# Filters.net
KiCad netlist of a schematic drawn in Altium Designer
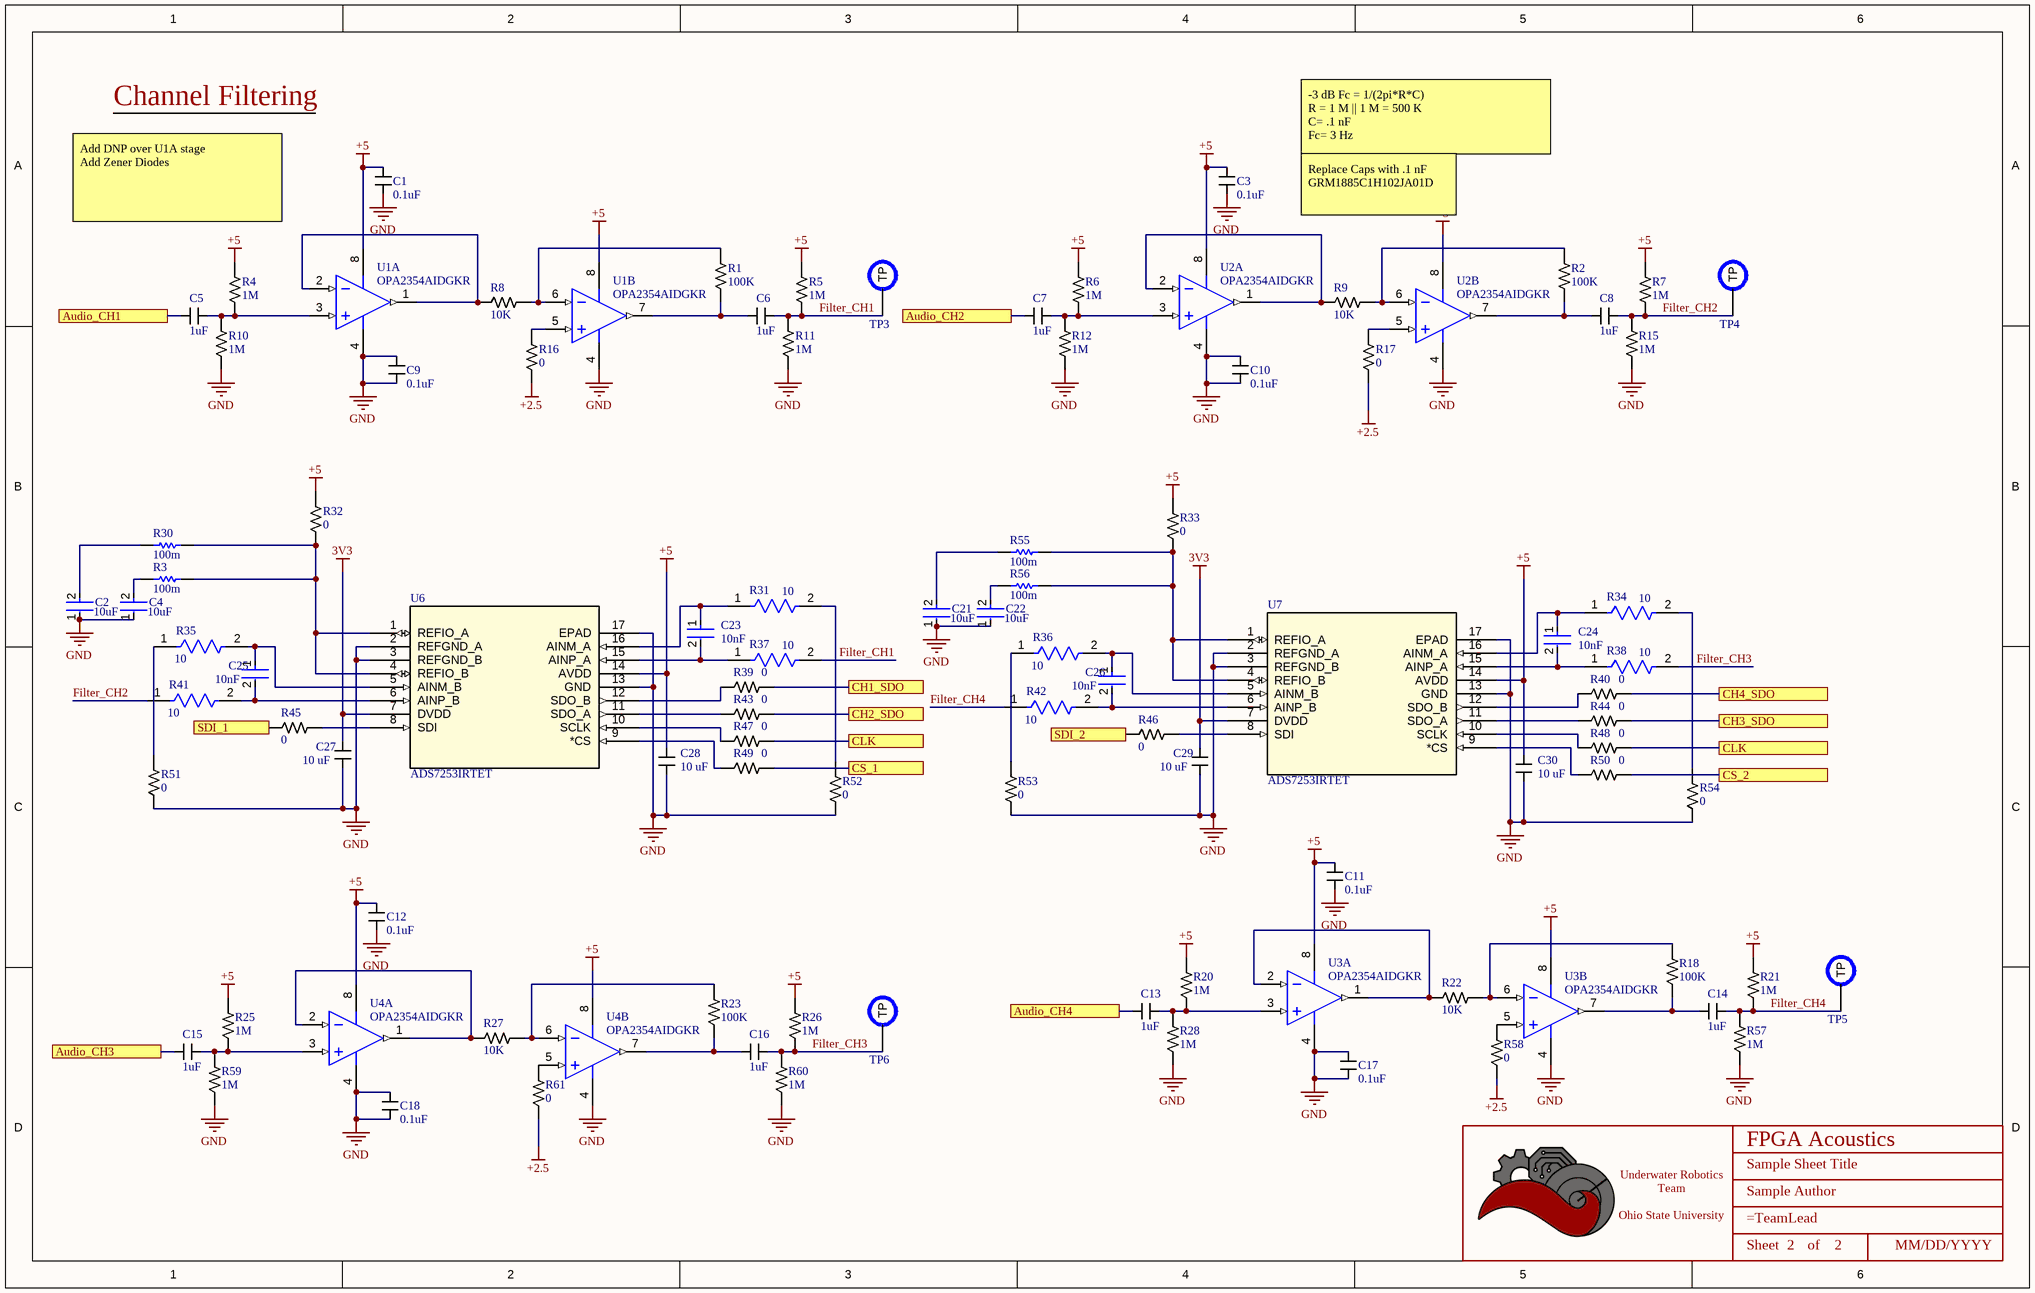
[diagram p0: Filters.SchDoc]

(export (version "E")
  (design (tool "Eeschema 10.0.6"))
  (components
    (comp (ref "C1")
      (value "0.1uF")
      (footprint "CAPACITOR_0603")
      (description "Cap 100nF 25V +/-10%\r\nCeramic 0603")
      (fields
        (field (name "TOLERANCE") "+/- 10%")
        (field (name "VOLTAGE") "6.3V")
        (field (name "MADE BY") "Flip B")
      )
      (libsource (lib "Capacitors") (part "CAPACITOR_0.1uF_0603_25V"))
    )
    (comp (ref "C2")
      (value "10uF")
      (footprint "FP-CL21B106KOQNNNE-MFG")
      (description "CAP CER 10UF 16V X7R 0805")
      (fields
        (field (name "MANUFACTURER PART NUMBER") "CL21B106KOQNNNE")
        (field (name "OCTOPART") "https://octopart.com/cl21b106koqnnne-samsung-19832289")
      )
      (libsource (lib "Altium Content Vault") (part "236180d848d6139a670b325ea6854c9"))
    )
    (comp (ref "C3")
      (value "0.1uF")
      (footprint "CAPACITOR_0603")
      (description "Cap 100nF 25V +/-10%\r\nCeramic 0603")
      (fields
        (field (name "TOLERANCE") "+/- 10%")
        (field (name "VOLTAGE") "6.3V")
        (field (name "MADE BY") "Flip B")
      )
      (libsource (lib "Capacitors") (part "CAPACITOR_0.1uF_0603_25V"))
    )
    (comp (ref "C4")
      (value "10uF")
      (footprint "FP-CL21B106KOQNNNE-MFG")
      (description "CAP CER 10UF 16V X7R 0805")
      (fields
        (field (name "MANUFACTURER PART NUMBER") "CL21B106KOQNNNE")
        (field (name "OCTOPART") "https://octopart.com/cl21b106koqnnne-samsung-19832289")
      )
      (libsource (lib "Altium Content Vault") (part "236180d848d6139a670b325ea6854c9"))
    )
    (comp (ref "C5")
      (value "1uF")
      (footprint "CAPACITOR_0603")
      (description "Cap 1uF 16V +/-10%\r\nCeramic 0603")
      (fields
        (field (name "TOLERANCE") "+/- 10%")
        (field (name "VOLTAGE") "16V")
        (field (name "MADE BY") "Flip B")
      )
      (libsource (lib "Capacitors") (part "CAPACITOR_1uF_0603"))
    )
    (comp (ref "C6")
      (value "1uF")
      (footprint "CAPACITOR_0603")
      (description "Cap 1uF 16V +/-10%\r\nCeramic 0603")
      (fields
        (field (name "TOLERANCE") "+/- 10%")
        (field (name "VOLTAGE") "16V")
        (field (name "MADE BY") "Flip B")
      )
      (libsource (lib "Capacitors") (part "CAPACITOR_1uF_0603"))
    )
    (comp (ref "C7")
      (value "1uF")
      (footprint "CAPACITOR_0603")
      (description "Cap 1uF 16V +/-10%\r\nCeramic 0603")
      (fields
        (field (name "TOLERANCE") "+/- 10%")
        (field (name "VOLTAGE") "16V")
        (field (name "MADE BY") "Flip B")
      )
      (libsource (lib "Capacitors") (part "CAPACITOR_1uF_0603"))
    )
    (comp (ref "C8")
      (value "1uF")
      (footprint "CAPACITOR_0603")
      (description "Cap 1uF 16V +/-10%\r\nCeramic 0603")
      (fields
        (field (name "TOLERANCE") "+/- 10%")
        (field (name "VOLTAGE") "16V")
        (field (name "MADE BY") "Flip B")
      )
      (libsource (lib "Capacitors") (part "CAPACITOR_1uF_0603"))
    )
    (comp (ref "C9")
      (value "0.1uF")
      (footprint "CAPACITOR_0603")
      (description "Cap 100nF 25V +/-10%\r\nCeramic 0603")
      (fields
        (field (name "TOLERANCE") "+/- 10%")
        (field (name "VOLTAGE") "6.3V")
        (field (name "MADE BY") "Flip B")
      )
      (libsource (lib "Capacitors") (part "CAPACITOR_0.1uF_0603_25V"))
    )
    (comp (ref "C10")
      (value "0.1uF")
      (footprint "CAPACITOR_0603")
      (description "Cap 100nF 25V +/-10%\r\nCeramic 0603")
      (fields
        (field (name "TOLERANCE") "+/- 10%")
        (field (name "VOLTAGE") "6.3V")
        (field (name "MADE BY") "Flip B")
      )
      (libsource (lib "Capacitors") (part "CAPACITOR_0.1uF_0603_25V"))
    )
    (comp (ref "C11")
      (value "0.1uF")
      (footprint "CAPACITOR_0603")
      (description "Cap 100nF 25V +/-10%\r\nCeramic 0603")
      (fields
        (field (name "TOLERANCE") "+/- 10%")
        (field (name "VOLTAGE") "6.3V")
        (field (name "MADE BY") "Flip B")
      )
      (libsource (lib "Capacitors") (part "CAPACITOR_0.1uF_0603_25V"))
    )
    (comp (ref "C12")
      (value "0.1uF")
      (footprint "CAPACITOR_0603")
      (description "Cap 100nF 25V +/-10%\r\nCeramic 0603")
      (fields
        (field (name "TOLERANCE") "+/- 10%")
        (field (name "VOLTAGE") "6.3V")
        (field (name "MADE BY") "Flip B")
      )
      (libsource (lib "Capacitors") (part "CAPACITOR_0.1uF_0603_25V"))
    )
    (comp (ref "C13")
      (value "1uF")
      (footprint "CAPACITOR_0603")
      (description "Cap 1uF 16V +/-10%\r\nCeramic 0603")
      (fields
        (field (name "TOLERANCE") "+/- 10%")
        (field (name "VOLTAGE") "16V")
        (field (name "MADE BY") "Flip B")
      )
      (libsource (lib "Capacitors") (part "CAPACITOR_1uF_0603"))
    )
    (comp (ref "C14")
      (value "1uF")
      (footprint "CAPACITOR_0603")
      (description "Cap 1uF 16V +/-10%\r\nCeramic 0603")
      (fields
        (field (name "TOLERANCE") "+/- 10%")
        (field (name "VOLTAGE") "16V")
        (field (name "MADE BY") "Flip B")
      )
      (libsource (lib "Capacitors") (part "CAPACITOR_1uF_0603"))
    )
    (comp (ref "C15")
      (value "1uF")
      (footprint "CAPACITOR_0603")
      (description "Cap 1uF 16V +/-10%\r\nCeramic 0603")
      (fields
        (field (name "TOLERANCE") "+/- 10%")
        (field (name "VOLTAGE") "16V")
        (field (name "MADE BY") "Flip B")
      )
      (libsource (lib "Capacitors") (part "CAPACITOR_1uF_0603"))
    )
    (comp (ref "C16")
      (value "1uF")
      (footprint "CAPACITOR_0603")
      (description "Cap 1uF 16V +/-10%\r\nCeramic 0603")
      (fields
        (field (name "TOLERANCE") "+/- 10%")
        (field (name "VOLTAGE") "16V")
        (field (name "MADE BY") "Flip B")
      )
      (libsource (lib "Capacitors") (part "CAPACITOR_1uF_0603"))
    )
    (comp (ref "C17")
      (value "0.1uF")
      (footprint "CAPACITOR_0603")
      (description "Cap 100nF 25V +/-10%\r\nCeramic 0603")
      (fields
        (field (name "TOLERANCE") "+/- 10%")
        (field (name "VOLTAGE") "6.3V")
        (field (name "MADE BY") "Flip B")
      )
      (libsource (lib "Capacitors") (part "CAPACITOR_0.1uF_0603_25V"))
    )
    (comp (ref "C18")
      (value "0.1uF")
      (footprint "CAPACITOR_0603")
      (description "Cap 100nF 25V +/-10%\r\nCeramic 0603")
      (fields
        (field (name "TOLERANCE") "+/- 10%")
        (field (name "VOLTAGE") "6.3V")
        (field (name "MADE BY") "Flip B")
      )
      (libsource (lib "Capacitors") (part "CAPACITOR_0.1uF_0603_25V"))
    )
    (comp (ref "C21")
      (value "10uF")
      (footprint "FP-CL21B106KOQNNNE-MFG")
      (description "CAP CER 10UF 16V X7R 0805")
      (fields
        (field (name "MANUFACTURER PART NUMBER") "CL21B106KOQNNNE")
        (field (name "OCTOPART") "https://octopart.com/cl21b106koqnnne-samsung-19832289")
      )
      (libsource (lib "Altium Content Vault") (part "236180d848d6139a670b325ea6854c9"))
    )
    (comp (ref "C22")
      (value "10uF")
      (footprint "FP-CL21B106KOQNNNE-MFG")
      (description "CAP CER 10UF 16V X7R 0805")
      (fields
        (field (name "MANUFACTURER PART NUMBER") "CL21B106KOQNNNE")
        (field (name "OCTOPART") "https://octopart.com/cl21b106koqnnne-samsung-19832289")
      )
      (libsource (lib "Altium Content Vault") (part "236180d848d6139a670b325ea6854c9"))
    )
    (comp (ref "C23")
      (value "GRM2195C1H103JA01D")
      (footprint "FP-GRM219-0_1-IPC_B")
      (description "Chip Multilayer Ceramic Capacitors for General Purpose, 0805, 10000pF, C0G, 30ppm/°C, 5%, 50V")
      (fields
        (field (name "VOLTAGE") "50V")
        (field (name "TOLERANCE") "5%")
        (field (name "CAPACITANCE") "10nF")
      )
      (libsource (lib "Altium Content Vault") (part "02cd4be3c70576c341d710602a673aa"))
    )
    (comp (ref "C24")
      (value "GRM2195C1H103JA01D")
      (footprint "FP-GRM219-0_1-IPC_B")
      (description "Chip Multilayer Ceramic Capacitors for General Purpose, 0805, 10000pF, C0G, 30ppm/°C, 5%, 50V")
      (fields
        (field (name "VOLTAGE") "50V")
        (field (name "TOLERANCE") "5%")
        (field (name "CAPACITANCE") "10nF")
      )
      (libsource (lib "Altium Content Vault") (part "02cd4be3c70576c341d710602a673aa"))
    )
    (comp (ref "C25")
      (value "GRM2195C1H103JA01D")
      (footprint "FP-GRM219-0_1-IPC_B")
      (description "Chip Multilayer Ceramic Capacitors for General Purpose, 0805, 10000pF, C0G, 30ppm/°C, 5%, 50V")
      (fields
        (field (name "VOLTAGE") "50V")
        (field (name "TOLERANCE") "5%")
        (field (name "CAPACITANCE") "10nF")
      )
      (libsource (lib "Altium Content Vault") (part "02cd4be3c70576c341d710602a673aa"))
    )
    (comp (ref "C26")
      (value "GRM2195C1H103JA01D")
      (footprint "FP-GRM219-0_1-IPC_B")
      (description "Chip Multilayer Ceramic Capacitors for General Purpose, 0805, 10000pF, C0G, 30ppm/°C, 5%, 50V")
      (fields
        (field (name "VOLTAGE") "50V")
        (field (name "TOLERANCE") "5%")
        (field (name "CAPACITANCE") "10nF")
      )
      (libsource (lib "Altium Content Vault") (part "02cd4be3c70576c341d710602a673aa"))
    )
    (comp (ref "C27")
      (value "10uF Ceramic 6.3V")
      (footprint "CAPACITOR_0603")
      (description "Cap 10uF 6.3V +/-20%\r\nCeramic 0603")
      (fields
        (field (name "TOLERANCE") "+/- 20%")
        (field (name "VOLTAGE") "6.3V")
        (field (name "VALUE (UF)") "10 uF")
        (field (name "MADE BY") "Flip B")
      )
      (libsource (lib "Capacitors") (part "CAPACITOR_10uF_0603"))
    )
    (comp (ref "C28")
      (value "10uF Ceramic 6.3V")
      (footprint "CAPACITOR_0603")
      (description "Cap 10uF 6.3V +/-20%\r\nCeramic 0603")
      (fields
        (field (name "TOLERANCE") "+/- 20%")
        (field (name "VOLTAGE") "6.3V")
        (field (name "VALUE (UF)") "10 uF")
        (field (name "MADE BY") "Flip B")
      )
      (libsource (lib "Capacitors") (part "CAPACITOR_10uF_0603"))
    )
    (comp (ref "C29")
      (value "10uF Ceramic 6.3V")
      (footprint "CAPACITOR_0603")
      (description "Cap 10uF 6.3V +/-20%\r\nCeramic 0603")
      (fields
        (field (name "TOLERANCE") "+/- 20%")
        (field (name "VOLTAGE") "6.3V")
        (field (name "VALUE (UF)") "10 uF")
        (field (name "MADE BY") "Flip B")
      )
      (libsource (lib "Capacitors") (part "CAPACITOR_10uF_0603"))
    )
    (comp (ref "C30")
      (value "10uF Ceramic 6.3V")
      (footprint "CAPACITOR_0603")
      (description "Cap 10uF 6.3V +/-20%\r\nCeramic 0603")
      (fields
        (field (name "TOLERANCE") "+/- 20%")
        (field (name "VOLTAGE") "6.3V")
        (field (name "VALUE (UF)") "10 uF")
        (field (name "MADE BY") "Flip B")
      )
      (libsource (lib "Capacitors") (part "CAPACITOR_10uF_0603"))
    )
    (comp (ref "R1")
      (value "100k Ohm 1% 1/16W")
      (footprint "RESISTOR_0402")
      (description "RES 100k OHM 1% 1/16W 0402")
      (fields
        (field (name "TOLERANCE") "+/- 1%")
        (field (name "VALUE  (OHMS)") "100K")
        (field (name "MADE BY") "Robert Pafford")
      )
      (libsource (lib "Resistors") (part "RESISTOR_100K_0402"))
    )
    (comp (ref "R2")
      (value "100k Ohm 1% 1/16W")
      (footprint "RESISTOR_0402")
      (description "RES 100k OHM 1% 1/16W 0402")
      (fields
        (field (name "TOLERANCE") "+/- 1%")
        (field (name "VALUE  (OHMS)") "100K")
        (field (name "MADE BY") "Robert Pafford")
      )
      (libsource (lib "Resistors") (part "RESISTOR_100K_0402"))
    )
    (comp (ref "R3")
      (value "100m")
      (footprint "RESC1005X40X25NL10T10")
      (fields (field (name "MANUFACTURER") "Yageo") (field (name "PART NUMBER") "RL0402JR-070R1L"))
      (libsource (lib "Altium Content Vault") (part "RES"))
    )
    (comp (ref "R4")
      (value "1M Ohm 1% 1/16W")
      (footprint "RESISTOR_0402")
      (description "RES 1M OHM 1% 1/16W 0402")
      (fields
        (field (name "TOLERANCE") "+/- 1%")
        (field (name "VALUE  (OHMS)") "1M")
        (field (name "MADE BY") "Robert Pafford")
      )
      (libsource (lib "Resistors") (part "RESISTOR_1M_0402"))
    )
    (comp (ref "R5")
      (value "1M Ohm 1% 1/16W")
      (footprint "RESISTOR_0402")
      (description "RES 1M OHM 1% 1/16W 0402")
      (fields
        (field (name "TOLERANCE") "+/- 1%")
        (field (name "VALUE  (OHMS)") "1M")
        (field (name "MADE BY") "Robert Pafford")
      )
      (libsource (lib "Resistors") (part "RESISTOR_1M_0402"))
    )
    (comp (ref "R6")
      (value "1M Ohm 1% 1/16W")
      (footprint "RESISTOR_0402")
      (description "RES 1M OHM 1% 1/16W 0402")
      (fields
        (field (name "TOLERANCE") "+/- 1%")
        (field (name "VALUE  (OHMS)") "1M")
        (field (name "MADE BY") "Robert Pafford")
      )
      (libsource (lib "Resistors") (part "RESISTOR_1M_0402"))
    )
    (comp (ref "R7")
      (value "1M Ohm 1% 1/16W")
      (footprint "RESISTOR_0402")
      (description "RES 1M OHM 1% 1/16W 0402")
      (fields
        (field (name "TOLERANCE") "+/- 1%")
        (field (name "VALUE  (OHMS)") "1M")
        (field (name "MADE BY") "Robert Pafford")
      )
      (libsource (lib "Resistors") (part "RESISTOR_1M_0402"))
    )
    (comp (ref "R8")
      (value "10k Ohm 1% 1/16W")
      (footprint "RESISTOR_0402")
      (description "RES 10k OHM 1% 1/16W 0402")
      (fields
        (field (name "TOLERANCE") "+/- 1%")
        (field (name "VALUE  (OHMS)") "10K")
        (field (name "MADE BY") "Robert Pafford")
      )
      (libsource (lib "Resistors") (part "RESISTOR_10K_0402"))
    )
    (comp (ref "R9")
      (value "10k Ohm 1% 1/16W")
      (footprint "RESISTOR_0402")
      (description "RES 10k OHM 1% 1/16W 0402")
      (fields
        (field (name "TOLERANCE") "+/- 1%")
        (field (name "VALUE  (OHMS)") "10K")
        (field (name "MADE BY") "Robert Pafford")
      )
      (libsource (lib "Resistors") (part "RESISTOR_10K_0402"))
    )
    (comp (ref "R10")
      (value "1M Ohm 1% 1/16W")
      (footprint "RESISTOR_0402")
      (description "RES 1M OHM 1% 1/16W 0402")
      (fields
        (field (name "TOLERANCE") "+/- 1%")
        (field (name "VALUE  (OHMS)") "1M")
        (field (name "MADE BY") "Robert Pafford")
      )
      (libsource (lib "Resistors") (part "RESISTOR_1M_0402"))
    )
    (comp (ref "R11")
      (value "1M Ohm 1% 1/16W")
      (footprint "RESISTOR_0402")
      (description "RES 1M OHM 1% 1/16W 0402")
      (fields
        (field (name "TOLERANCE") "+/- 1%")
        (field (name "VALUE  (OHMS)") "1M")
        (field (name "MADE BY") "Robert Pafford")
      )
      (libsource (lib "Resistors") (part "RESISTOR_1M_0402"))
    )
    (comp (ref "R12")
      (value "1M Ohm 1% 1/16W")
      (footprint "RESISTOR_0402")
      (description "RES 1M OHM 1% 1/16W 0402")
      (fields
        (field (name "TOLERANCE") "+/- 1%")
        (field (name "VALUE  (OHMS)") "1M")
        (field (name "MADE BY") "Robert Pafford")
      )
      (libsource (lib "Resistors") (part "RESISTOR_1M_0402"))
    )
    (comp (ref "R15")
      (value "1M Ohm 1% 1/16W")
      (footprint "RESISTOR_0402")
      (description "RES 1M OHM 1% 1/16W 0402")
      (fields
        (field (name "TOLERANCE") "+/- 1%")
        (field (name "VALUE  (OHMS)") "1M")
        (field (name "MADE BY") "Robert Pafford")
      )
      (libsource (lib "Resistors") (part "RESISTOR_1M_0402"))
    )
    (comp (ref "R16")
      (value "0 Ohm 1% 1/16W")
      (footprint "RESISTOR_0402")
      (description "RES 0 OHM 1% 1/16W 0402")
      (fields
        (field (name "TOLERANCE") "+/- 1%")
        (field (name "VALUE  (OHMS)") "0")
        (field (name "MADE BY") "Robert Pafford")
      )
      (libsource (lib "Resistors") (part "RESISTOR_0_0402"))
    )
    (comp (ref "R17")
      (value "0 Ohm 1% 1/16W")
      (footprint "RESISTOR_0402")
      (description "RES 0 OHM 1% 1/16W 0402")
      (fields
        (field (name "TOLERANCE") "+/- 1%")
        (field (name "VALUE  (OHMS)") "0")
        (field (name "MADE BY") "Robert Pafford")
      )
      (libsource (lib "Resistors") (part "RESISTOR_0_0402"))
    )
    (comp (ref "R18")
      (value "100k Ohm 1% 1/16W")
      (footprint "RESISTOR_0402")
      (description "RES 100k OHM 1% 1/16W 0402")
      (fields
        (field (name "TOLERANCE") "+/- 1%")
        (field (name "VALUE  (OHMS)") "100K")
        (field (name "MADE BY") "Robert Pafford")
      )
      (libsource (lib "Resistors") (part "RESISTOR_100K_0402"))
    )
    (comp (ref "R20")
      (value "1M Ohm 1% 1/16W")
      (footprint "RESISTOR_0402")
      (description "RES 1M OHM 1% 1/16W 0402")
      (fields
        (field (name "TOLERANCE") "+/- 1%")
        (field (name "VALUE  (OHMS)") "1M")
        (field (name "MADE BY") "Robert Pafford")
      )
      (libsource (lib "Resistors") (part "RESISTOR_1M_0402"))
    )
    (comp (ref "R21")
      (value "1M Ohm 1% 1/16W")
      (footprint "RESISTOR_0402")
      (description "RES 1M OHM 1% 1/16W 0402")
      (fields
        (field (name "TOLERANCE") "+/- 1%")
        (field (name "VALUE  (OHMS)") "1M")
        (field (name "MADE BY") "Robert Pafford")
      )
      (libsource (lib "Resistors") (part "RESISTOR_1M_0402"))
    )
    (comp (ref "R22")
      (value "10k Ohm 1% 1/16W")
      (footprint "RESISTOR_0402")
      (description "RES 10k OHM 1% 1/16W 0402")
      (fields
        (field (name "TOLERANCE") "+/- 1%")
        (field (name "VALUE  (OHMS)") "10K")
        (field (name "MADE BY") "Robert Pafford")
      )
      (libsource (lib "Resistors") (part "RESISTOR_10K_0402"))
    )
    (comp (ref "R23")
      (value "100k Ohm 1% 1/16W")
      (footprint "RESISTOR_0402")
      (description "RES 100k OHM 1% 1/16W 0402")
      (fields
        (field (name "TOLERANCE") "+/- 1%")
        (field (name "VALUE  (OHMS)") "100K")
        (field (name "MADE BY") "Robert Pafford")
      )
      (libsource (lib "Resistors") (part "RESISTOR_100K_0402"))
    )
    (comp (ref "R25")
      (value "1M Ohm 1% 1/16W")
      (footprint "RESISTOR_0402")
      (description "RES 1M OHM 1% 1/16W 0402")
      (fields
        (field (name "TOLERANCE") "+/- 1%")
        (field (name "VALUE  (OHMS)") "1M")
        (field (name "MADE BY") "Robert Pafford")
      )
      (libsource (lib "Resistors") (part "RESISTOR_1M_0402"))
    )
    (comp (ref "R26")
      (value "1M Ohm 1% 1/16W")
      (footprint "RESISTOR_0402")
      (description "RES 1M OHM 1% 1/16W 0402")
      (fields
        (field (name "TOLERANCE") "+/- 1%")
        (field (name "VALUE  (OHMS)") "1M")
        (field (name "MADE BY") "Robert Pafford")
      )
      (libsource (lib "Resistors") (part "RESISTOR_1M_0402"))
    )
    (comp (ref "R27")
      (value "10k Ohm 1% 1/16W")
      (footprint "RESISTOR_0402")
      (description "RES 10k OHM 1% 1/16W 0402")
      (fields
        (field (name "TOLERANCE") "+/- 1%")
        (field (name "VALUE  (OHMS)") "10K")
        (field (name "MADE BY") "Robert Pafford")
      )
      (libsource (lib "Resistors") (part "RESISTOR_10K_0402"))
    )
    (comp (ref "R28")
      (value "1M Ohm 1% 1/16W")
      (footprint "RESISTOR_0402")
      (description "RES 1M OHM 1% 1/16W 0402")
      (fields
        (field (name "TOLERANCE") "+/- 1%")
        (field (name "VALUE  (OHMS)") "1M")
        (field (name "MADE BY") "Robert Pafford")
      )
      (libsource (lib "Resistors") (part "RESISTOR_1M_0402"))
    )
    (comp (ref "R30")
      (value "100m")
      (footprint "RESC1005X40X25NL10T10")
      (fields (field (name "MANUFACTURER") "Yageo") (field (name "PART NUMBER") "RL0402JR-070R1L"))
      (libsource (lib "Altium Content Vault") (part "RES"))
    )
    (comp (ref "R31")
      (value "RMCF0603FT10R0")
      (footprint "FP-RMCF0603-MFG")
      (description "10Ω ±1% 0.1W 0603 Thick Film Chip Resistor AEC-Q200 compliant")
      (fields (field (name "TOLERANCE") "1%") (field (name "RESISTANCE") "10"))
      (libsource (lib "Altium Content Vault") (part "1029c3af85768c4190bb7ad29bc67b5"))
    )
    (comp (ref "R32")
      (value "0 Ohm 1% 1/16W")
      (footprint "RESISTOR_0402")
      (description "RES 0 OHM 1% 1/16W 0402")
      (fields
        (field (name "TOLERANCE") "+/- 1%")
        (field (name "VALUE  (OHMS)") "0")
        (field (name "MADE BY") "Robert Pafford")
      )
      (libsource (lib "Resistors") (part "RESISTOR_0_0402"))
    )
    (comp (ref "R33")
      (value "0 Ohm 1% 1/16W")
      (footprint "RESISTOR_0402")
      (description "RES 0 OHM 1% 1/16W 0402")
      (fields
        (field (name "TOLERANCE") "+/- 1%")
        (field (name "VALUE  (OHMS)") "0")
        (field (name "MADE BY") "Robert Pafford")
      )
      (libsource (lib "Resistors") (part "RESISTOR_0_0402"))
    )
    (comp (ref "R34")
      (value "RMCF0603FT10R0")
      (footprint "FP-RMCF0603-MFG")
      (description "10Ω ±1% 0.1W 0603 Thick Film Chip Resistor AEC-Q200 compliant")
      (fields (field (name "TOLERANCE") "1%") (field (name "RESISTANCE") "10"))
      (libsource (lib "Altium Content Vault") (part "1029c3af85768c4190bb7ad29bc67b5"))
    )
    (comp (ref "R35")
      (value "RMCF0603FT10R0")
      (footprint "FP-RMCF0603-MFG")
      (description "10Ω ±1% 0.1W 0603 Thick Film Chip Resistor AEC-Q200 compliant")
      (fields (field (name "TOLERANCE") "1%") (field (name "RESISTANCE") "10"))
      (libsource (lib "Altium Content Vault") (part "1029c3af85768c4190bb7ad29bc67b5"))
    )
    (comp (ref "R36")
      (value "RMCF0603FT10R0")
      (footprint "FP-RMCF0603-MFG")
      (description "10Ω ±1% 0.1W 0603 Thick Film Chip Resistor AEC-Q200 compliant")
      (fields (field (name "TOLERANCE") "1%") (field (name "RESISTANCE") "10"))
      (libsource (lib "Altium Content Vault") (part "1029c3af85768c4190bb7ad29bc67b5"))
    )
    (comp (ref "R37")
      (value "RMCF0603FT10R0")
      (footprint "FP-RMCF0603-MFG")
      (description "10Ω ±1% 0.1W 0603 Thick Film Chip Resistor AEC-Q200 compliant")
      (fields (field (name "TOLERANCE") "1%") (field (name "RESISTANCE") "10"))
      (libsource (lib "Altium Content Vault") (part "1029c3af85768c4190bb7ad29bc67b5"))
    )
    (comp (ref "R38")
      (value "RMCF0603FT10R0")
      (footprint "FP-RMCF0603-MFG")
      (description "10Ω ±1% 0.1W 0603 Thick Film Chip Resistor AEC-Q200 compliant")
      (fields (field (name "TOLERANCE") "1%") (field (name "RESISTANCE") "10"))
      (libsource (lib "Altium Content Vault") (part "1029c3af85768c4190bb7ad29bc67b5"))
    )
    (comp (ref "R39")
      (value "0 Ohm 1% 1/16W")
      (footprint "RESISTOR_0402")
      (description "RES 0 OHM 1% 1/16W 0402")
      (fields
        (field (name "TOLERANCE") "+/- 1%")
        (field (name "VALUE  (OHMS)") "0")
        (field (name "MADE BY") "Robert Pafford")
      )
      (libsource (lib "Resistors") (part "RESISTOR_0_0402"))
    )
    (comp (ref "R40")
      (value "0 Ohm 1% 1/16W")
      (footprint "RESISTOR_0402")
      (description "RES 0 OHM 1% 1/16W 0402")
      (fields
        (field (name "TOLERANCE") "+/- 1%")
        (field (name "VALUE  (OHMS)") "0")
        (field (name "MADE BY") "Robert Pafford")
      )
      (libsource (lib "Resistors") (part "RESISTOR_0_0402"))
    )
    (comp (ref "R41")
      (value "RMCF0603FT10R0")
      (footprint "FP-RMCF0603-MFG")
      (description "10Ω ±1% 0.1W 0603 Thick Film Chip Resistor AEC-Q200 compliant")
      (fields (field (name "TOLERANCE") "1%") (field (name "RESISTANCE") "10"))
      (libsource (lib "Altium Content Vault") (part "1029c3af85768c4190bb7ad29bc67b5"))
    )
    (comp (ref "R42")
      (value "RMCF0603FT10R0")
      (footprint "FP-RMCF0603-MFG")
      (description "10Ω ±1% 0.1W 0603 Thick Film Chip Resistor AEC-Q200 compliant")
      (fields (field (name "TOLERANCE") "1%") (field (name "RESISTANCE") "10"))
      (libsource (lib "Altium Content Vault") (part "1029c3af85768c4190bb7ad29bc67b5"))
    )
    (comp (ref "R43")
      (value "0 Ohm 1% 1/16W")
      (footprint "RESISTOR_0402")
      (description "RES 0 OHM 1% 1/16W 0402")
      (fields
        (field (name "TOLERANCE") "+/- 1%")
        (field (name "VALUE  (OHMS)") "0")
        (field (name "MADE BY") "Robert Pafford")
      )
      (libsource (lib "Resistors") (part "RESISTOR_0_0402"))
    )
    (comp (ref "R44")
      (value "0 Ohm 1% 1/16W")
      (footprint "RESISTOR_0402")
      (description "RES 0 OHM 1% 1/16W 0402")
      (fields
        (field (name "TOLERANCE") "+/- 1%")
        (field (name "VALUE  (OHMS)") "0")
        (field (name "MADE BY") "Robert Pafford")
      )
      (libsource (lib "Resistors") (part "RESISTOR_0_0402"))
    )
    (comp (ref "R45")
      (value "0 Ohm 1% 1/16W")
      (footprint "RESISTOR_0402")
      (description "RES 0 OHM 1% 1/16W 0402")
      (fields
        (field (name "TOLERANCE") "+/- 1%")
        (field (name "VALUE  (OHMS)") "0")
        (field (name "MADE BY") "Robert Pafford")
      )
      (libsource (lib "Resistors") (part "RESISTOR_0_0402"))
    )
    (comp (ref "R46")
      (value "0 Ohm 1% 1/16W")
      (footprint "RESISTOR_0402")
      (description "RES 0 OHM 1% 1/16W 0402")
      (fields
        (field (name "TOLERANCE") "+/- 1%")
        (field (name "VALUE  (OHMS)") "0")
        (field (name "MADE BY") "Robert Pafford")
      )
      (libsource (lib "Resistors") (part "RESISTOR_0_0402"))
    )
    (comp (ref "R47")
      (value "0 Ohm 1% 1/16W")
      (footprint "RESISTOR_0402")
      (description "RES 0 OHM 1% 1/16W 0402")
      (fields
        (field (name "TOLERANCE") "+/- 1%")
        (field (name "VALUE  (OHMS)") "0")
        (field (name "MADE BY") "Robert Pafford")
      )
      (libsource (lib "Resistors") (part "RESISTOR_0_0402"))
    )
    (comp (ref "R48")
      (value "0 Ohm 1% 1/16W")
      (footprint "RESISTOR_0402")
      (description "RES 0 OHM 1% 1/16W 0402")
      (fields
        (field (name "TOLERANCE") "+/- 1%")
        (field (name "VALUE  (OHMS)") "0")
        (field (name "MADE BY") "Robert Pafford")
      )
      (libsource (lib "Resistors") (part "RESISTOR_0_0402"))
    )
    (comp (ref "R49")
      (value "0 Ohm 1% 1/16W")
      (footprint "RESISTOR_0402")
      (description "RES 0 OHM 1% 1/16W 0402")
      (fields
        (field (name "TOLERANCE") "+/- 1%")
        (field (name "VALUE  (OHMS)") "0")
        (field (name "MADE BY") "Robert Pafford")
      )
      (libsource (lib "Resistors") (part "RESISTOR_0_0402"))
    )
    (comp (ref "R50")
      (value "0 Ohm 1% 1/16W")
      (footprint "RESISTOR_0402")
      (description "RES 0 OHM 1% 1/16W 0402")
      (fields
        (field (name "TOLERANCE") "+/- 1%")
        (field (name "VALUE  (OHMS)") "0")
        (field (name "MADE BY") "Robert Pafford")
      )
      (libsource (lib "Resistors") (part "RESISTOR_0_0402"))
    )
    (comp (ref "R51")
      (value "0 Ohm 1% 1/16W")
      (footprint "RESISTOR_0402")
      (description "RES 0 OHM 1% 1/16W 0402")
      (fields
        (field (name "TOLERANCE") "+/- 1%")
        (field (name "VALUE  (OHMS)") "0")
        (field (name "MADE BY") "Robert Pafford")
      )
      (libsource (lib "Resistors") (part "RESISTOR_0_0402"))
    )
    (comp (ref "R52")
      (value "0 Ohm 1% 1/16W")
      (footprint "RESISTOR_0402")
      (description "RES 0 OHM 1% 1/16W 0402")
      (fields
        (field (name "TOLERANCE") "+/- 1%")
        (field (name "VALUE  (OHMS)") "0")
        (field (name "MADE BY") "Robert Pafford")
      )
      (libsource (lib "Resistors") (part "RESISTOR_0_0402"))
    )
    (comp (ref "R53")
      (value "0 Ohm 1% 1/16W")
      (footprint "RESISTOR_0402")
      (description "RES 0 OHM 1% 1/16W 0402")
      (fields
        (field (name "TOLERANCE") "+/- 1%")
        (field (name "VALUE  (OHMS)") "0")
        (field (name "MADE BY") "Robert Pafford")
      )
      (libsource (lib "Resistors") (part "RESISTOR_0_0402"))
    )
    (comp (ref "R54")
      (value "0 Ohm 1% 1/16W")
      (footprint "RESISTOR_0402")
      (description "RES 0 OHM 1% 1/16W 0402")
      (fields
        (field (name "TOLERANCE") "+/- 1%")
        (field (name "VALUE  (OHMS)") "0")
        (field (name "MADE BY") "Robert Pafford")
      )
      (libsource (lib "Resistors") (part "RESISTOR_0_0402"))
    )
    (comp (ref "R55")
      (value "100m")
      (footprint "RESC1005X40X25NL10T10")
      (fields (field (name "MANUFACTURER") "Yageo") (field (name "PART NUMBER") "RL0402JR-070R1L"))
      (libsource (lib "Altium Content Vault") (part "RES"))
    )
    (comp (ref "R56")
      (value "100m")
      (footprint "RESC1005X40X25NL10T10")
      (fields (field (name "MANUFACTURER") "Yageo") (field (name "PART NUMBER") "RL0402JR-070R1L"))
      (libsource (lib "Altium Content Vault") (part "RES"))
    )
    (comp (ref "R57")
      (value "1M Ohm 1% 1/16W")
      (footprint "RESISTOR_0402")
      (description "RES 1M OHM 1% 1/16W 0402")
      (fields
        (field (name "TOLERANCE") "+/- 1%")
        (field (name "VALUE  (OHMS)") "1M")
        (field (name "MADE BY") "Robert Pafford")
      )
      (libsource (lib "Resistors") (part "RESISTOR_1M_0402"))
    )
    (comp (ref "R58")
      (value "0 Ohm 1% 1/16W")
      (footprint "RESISTOR_0402")
      (description "RES 0 OHM 1% 1/16W 0402")
      (fields
        (field (name "TOLERANCE") "+/- 1%")
        (field (name "VALUE  (OHMS)") "0")
        (field (name "MADE BY") "Robert Pafford")
      )
      (libsource (lib "Resistors") (part "RESISTOR_0_0402"))
    )
    (comp (ref "R59")
      (value "1M Ohm 1% 1/16W")
      (footprint "RESISTOR_0402")
      (description "RES 1M OHM 1% 1/16W 0402")
      (fields
        (field (name "TOLERANCE") "+/- 1%")
        (field (name "VALUE  (OHMS)") "1M")
        (field (name "MADE BY") "Robert Pafford")
      )
      (libsource (lib "Resistors") (part "RESISTOR_1M_0402"))
    )
    (comp (ref "R60")
      (value "1M Ohm 1% 1/16W")
      (footprint "RESISTOR_0402")
      (description "RES 1M OHM 1% 1/16W 0402")
      (fields
        (field (name "TOLERANCE") "+/- 1%")
        (field (name "VALUE  (OHMS)") "1M")
        (field (name "MADE BY") "Robert Pafford")
      )
      (libsource (lib "Resistors") (part "RESISTOR_1M_0402"))
    )
    (comp (ref "R61")
      (value "0 Ohm 1% 1/16W")
      (footprint "RESISTOR_0402")
      (description "RES 0 OHM 1% 1/16W 0402")
      (fields
        (field (name "TOLERANCE") "+/- 1%")
        (field (name "VALUE  (OHMS)") "0")
        (field (name "MADE BY") "Robert Pafford")
      )
      (libsource (lib "Resistors") (part "RESISTOR_0_0402"))
    )
    (comp (ref "TP3")
      (value "PCB Test Point")
      (footprint "TESTPOINT_1.2MM")
      (fields (field (name "MADE BY") "Robert Pafford"))
      (libsource (lib "Connectors") (part "TESTPOINT"))
    )
    (comp (ref "TP4")
      (value "PCB Test Point")
      (footprint "TESTPOINT_1.2MM")
      (fields (field (name "MADE BY") "Robert Pafford"))
      (libsource (lib "Connectors") (part "TESTPOINT"))
    )
    (comp (ref "TP5")
      (value "PCB Test Point")
      (footprint "TESTPOINT_1.2MM")
      (fields (field (name "MADE BY") "Robert Pafford"))
      (libsource (lib "Connectors") (part "TESTPOINT"))
    )
    (comp (ref "TP6")
      (value "PCB Test Point")
      (footprint "TESTPOINT_1.2MM")
      (fields (field (name "MADE BY") "Robert Pafford"))
      (libsource (lib "Connectors") (part "TESTPOINT"))
    )
    (comp (ref "U1")
      (value "OPA2354AIDGKR")
      (footprint "DGK0008A_M")
      (fields (field (name "MANUFACTURER") "Texas Instruments"))
      (libsource (lib "Altium Content Vault") (part "TI-OPA2354DGK8"))
    )
    (comp (ref "U2")
      (value "OPA2354AIDGKR")
      (footprint "DGK0008A_M")
      (fields (field (name "MANUFACTURER") "Texas Instruments"))
      (libsource (lib "Altium Content Vault") (part "TI-OPA2354DGK8"))
    )
    (comp (ref "U3")
      (value "OPA2354AIDGKR")
      (footprint "DGK0008A_M")
      (fields (field (name "MANUFACTURER") "Texas Instruments"))
      (libsource (lib "Altium Content Vault") (part "TI-OPA2354DGK8"))
    )
    (comp (ref "U4")
      (value "OPA2354AIDGKR")
      (footprint "DGK0008A_M")
      (fields (field (name "MANUFACTURER") "Texas Instruments"))
      (libsource (lib "Altium Content Vault") (part "TI-OPA2354DGK8"))
    )
    (comp (ref "U6")
      (value "ADS7253IRTET")
      (footprint "WQFN-16")
      (fields (field (name "MANUFACTURER") "TI") (field (name "CREATED BY") "John Ulm"))
      (libsource (lib "Integrated Circuits") (part "ADS7253IRTET"))
    )
    (comp (ref "U7")
      (value "ADS7253IRTET")
      (footprint "WQFN-16")
      (fields (field (name "MANUFACTURER") "TI") (field (name "CREATED BY") "John Ulm"))
      (libsource (lib "Integrated Circuits") (part "ADS7253IRTET"))
    )
  )
  (nets
    (net (code "1") (name "+2.5") (class "Default")
      (node (ref "R16") (pin "2") (pinfunction "2_2") (pintype "passive"))
      (node (ref "R17") (pin "2") (pinfunction "2_2") (pintype "passive"))
      (node (ref "R58") (pin "2") (pinfunction "2_2") (pintype "passive"))
      (node (ref "R61") (pin "2") (pinfunction "2_2") (pintype "passive"))
    )
    (net (code "2") (name "+5") (class "Default")
      (node (ref "C1") (pin "1") (pinfunction "1_1") (pintype "passive"))
      (node (ref "C11") (pin "1") (pinfunction "1_1") (pintype "passive"))
      (node (ref "C12") (pin "1") (pinfunction "1_1") (pintype "passive"))
      (node (ref "C28") (pin "2") (pinfunction "2_2") (pintype "passive"))
      (node (ref "C3") (pin "1") (pinfunction "1_1") (pintype "passive"))
      (node (ref "C30") (pin "2") (pinfunction "2_2") (pintype "passive"))
      (node (ref "R20") (pin "1") (pinfunction "1_1") (pintype "passive"))
      (node (ref "R21") (pin "1") (pinfunction "1_1") (pintype "passive"))
      (node (ref "R25") (pin "1") (pinfunction "1_1") (pintype "passive"))
      (node (ref "R26") (pin "1") (pinfunction "1_1") (pintype "passive"))
      (node (ref "R32") (pin "1") (pinfunction "1_1") (pintype "passive"))
      (node (ref "R33") (pin "1") (pinfunction "1_1") (pintype "passive"))
      (node (ref "R4") (pin "1") (pinfunction "1_1") (pintype "passive"))
      (node (ref "R5") (pin "1") (pinfunction "1_1") (pintype "passive"))
      (node (ref "R6") (pin "1") (pinfunction "1_1") (pintype "passive"))
      (node (ref "R7") (pin "1") (pinfunction "1_1") (pintype "passive"))
      (node (ref "U1") (pin "8") (pinfunction "V+_8") (pintype "power_in"))
      (node (ref "U2") (pin "8") (pinfunction "V+_8") (pintype "power_in"))
      (node (ref "U3") (pin "8") (pinfunction "V+_8") (pintype "power_in"))
      (node (ref "U4") (pin "8") (pinfunction "V+_8") (pintype "power_in"))
      (node (ref "U6") (pin "14") (pinfunction "AVDD_14") (pintype "power_in"))
      (node (ref "U7") (pin "14") (pinfunction "AVDD_14") (pintype "power_in"))
    )
    (net (code "3") (name "/Audio_CH1") (class "Default")
      (node (ref "C5") (pin "2") (pinfunction "2_2") (pintype "passive"))
    )
    (net (code "4") (name "/Audio_CH2") (class "Default")
      (node (ref "C7") (pin "2") (pinfunction "2_2") (pintype "passive"))
    )
    (net (code "5") (name "/Audio_CH3") (class "Default")
      (node (ref "C15") (pin "2") (pinfunction "2_2") (pintype "passive"))
    )
    (net (code "6") (name "/Audio_CH4") (class "Default")
      (node (ref "C13") (pin "2") (pinfunction "2_2") (pintype "passive"))
    )
    (net (code "7") (name "/CH1_SDO") (class "Default")
      (node (ref "R39") (pin "1") (pinfunction "1_1") (pintype "passive"))
    )
    (net (code "8") (name "/CH2_SDO") (class "Default")
      (node (ref "R43") (pin "1") (pinfunction "1_1") (pintype "passive"))
    )
    (net (code "9") (name "/CH3_SDO") (class "Default")
      (node (ref "R44") (pin "1") (pinfunction "1_1") (pintype "passive"))
    )
    (net (code "10") (name "/CH4_SDO") (class "Default")
      (node (ref "R40") (pin "1") (pinfunction "1_1") (pintype "passive"))
    )
    (net (code "11") (name "/CLK") (class "Default")
      (node (ref "R47") (pin "1") (pinfunction "1_1") (pintype "passive"))
      (node (ref "R48") (pin "1") (pinfunction "1_1") (pintype "passive"))
    )
    (net (code "12") (name "/CS_1") (class "Default")
      (node (ref "R49") (pin "1") (pinfunction "1_1") (pintype "passive"))
    )
    (net (code "13") (name "/CS_2") (class "Default")
      (node (ref "R50") (pin "1") (pinfunction "1_1") (pintype "passive"))
    )
    (net (code "14") (name "/Filter_CH1") (class "Default")
      (node (ref "C6") (pin "1") (pinfunction "1_1") (pintype "passive"))
      (node (ref "R11") (pin "1") (pinfunction "1_1") (pintype "passive"))
      (node (ref "R37") (pin "2") (pinfunction "2_2") (pintype "passive"))
      (node (ref "R5") (pin "2") (pinfunction "2_2") (pintype "passive"))
      (node (ref "TP3") (pin "TP") (pinfunction "TP_TP") (pintype "passive"))
    )
    (net (code "15") (name "/Filter_CH2") (class "Default")
      (node (ref "C8") (pin "1") (pinfunction "1_1") (pintype "passive"))
      (node (ref "R15") (pin "1") (pinfunction "1_1") (pintype "passive"))
      (node (ref "R41") (pin "1") (pinfunction "1_1") (pintype "passive"))
      (node (ref "R7") (pin "2") (pinfunction "2_2") (pintype "passive"))
      (node (ref "TP4") (pin "TP") (pinfunction "TP_TP") (pintype "passive"))
    )
    (net (code "16") (name "/Filter_CH3") (class "Default")
      (node (ref "C16") (pin "1") (pinfunction "1_1") (pintype "passive"))
      (node (ref "R26") (pin "2") (pinfunction "2_2") (pintype "passive"))
      (node (ref "R38") (pin "2") (pinfunction "2_2") (pintype "passive"))
      (node (ref "R60") (pin "1") (pinfunction "1_1") (pintype "passive"))
      (node (ref "TP6") (pin "TP") (pinfunction "TP_TP") (pintype "passive"))
    )
    (net (code "17") (name "/Filter_CH4") (class "Default")
      (node (ref "C14") (pin "1") (pinfunction "1_1") (pintype "passive"))
      (node (ref "R21") (pin "2") (pinfunction "2_2") (pintype "passive"))
      (node (ref "R42") (pin "1") (pinfunction "1_1") (pintype "passive"))
      (node (ref "R57") (pin "1") (pinfunction "1_1") (pintype "passive"))
      (node (ref "TP5") (pin "TP") (pinfunction "TP_TP") (pintype "passive"))
    )
    (net (code "18") (name "/SDI_1") (class "Default")
      (node (ref "R45") (pin "2") (pinfunction "2_2") (pintype "passive"))
    )
    (net (code "19") (name "/SDI_2") (class "Default")
      (node (ref "R46") (pin "2") (pinfunction "2_2") (pintype "passive"))
    )
    (net (code "20") (name "3V3") (class "Default")
      (node (ref "C27") (pin "2") (pinfunction "2_2") (pintype "passive"))
      (node (ref "C29") (pin "2") (pinfunction "2_2") (pintype "passive"))
      (node (ref "U6") (pin "7") (pinfunction "DVDD_7") (pintype "power_in"))
      (node (ref "U7") (pin "7") (pinfunction "DVDD_7") (pintype "power_in"))
    )
    (net (code "21") (name "GND") (class "Default")
      (node (ref "C1") (pin "2") (pinfunction "2_2") (pintype "passive"))
      (node (ref "C10") (pin "1") (pinfunction "1_1") (pintype "passive"))
      (node (ref "C10") (pin "2") (pinfunction "2_2") (pintype "passive"))
      (node (ref "C11") (pin "2") (pinfunction "2_2") (pintype "passive"))
      (node (ref "C12") (pin "2") (pinfunction "2_2") (pintype "passive"))
      (node (ref "C17") (pin "1") (pinfunction "1_1") (pintype "passive"))
      (node (ref "C17") (pin "2") (pinfunction "2_2") (pintype "passive"))
      (node (ref "C18") (pin "1") (pinfunction "1_1") (pintype "passive"))
      (node (ref "C18") (pin "2") (pinfunction "2_2") (pintype "passive"))
      (node (ref "C2") (pin "1") (pinfunction "1_1") (pintype "passive"))
      (node (ref "C21") (pin "1") (pinfunction "1_1") (pintype "passive"))
      (node (ref "C22") (pin "1") (pinfunction "1_1") (pintype "passive"))
      (node (ref "C27") (pin "1") (pinfunction "1_1") (pintype "passive"))
      (node (ref "C28") (pin "1") (pinfunction "1_1") (pintype "passive"))
      (node (ref "C29") (pin "1") (pinfunction "1_1") (pintype "passive"))
      (node (ref "C3") (pin "2") (pinfunction "2_2") (pintype "passive"))
      (node (ref "C30") (pin "1") (pinfunction "1_1") (pintype "passive"))
      (node (ref "C4") (pin "1") (pinfunction "1_1") (pintype "passive"))
      (node (ref "C9") (pin "1") (pinfunction "1_1") (pintype "passive"))
      (node (ref "C9") (pin "2") (pinfunction "2_2") (pintype "passive"))
      (node (ref "R10") (pin "2") (pinfunction "2_2") (pintype "passive"))
      (node (ref "R11") (pin "2") (pinfunction "2_2") (pintype "passive"))
      (node (ref "R12") (pin "2") (pinfunction "2_2") (pintype "passive"))
      (node (ref "R15") (pin "2") (pinfunction "2_2") (pintype "passive"))
      (node (ref "R28") (pin "2") (pinfunction "2_2") (pintype "passive"))
      (node (ref "R51") (pin "2") (pinfunction "2_2") (pintype "passive"))
      (node (ref "R52") (pin "2") (pinfunction "2_2") (pintype "passive"))
      (node (ref "R53") (pin "2") (pinfunction "2_2") (pintype "passive"))
      (node (ref "R54") (pin "2") (pinfunction "2_2") (pintype "passive"))
      (node (ref "R57") (pin "2") (pinfunction "2_2") (pintype "passive"))
      (node (ref "R59") (pin "2") (pinfunction "2_2") (pintype "passive"))
      (node (ref "R60") (pin "2") (pinfunction "2_2") (pintype "passive"))
      (node (ref "U1") (pin "4") (pinfunction "V-_4") (pintype "power_in"))
      (node (ref "U2") (pin "4") (pinfunction "V-_4") (pintype "power_in"))
      (node (ref "U3") (pin "4") (pinfunction "V-_4") (pintype "power_in"))
      (node (ref "U4") (pin "4") (pinfunction "V-_4") (pintype "power_in"))
      (node (ref "U6") (pin "13") (pinfunction "GND_13") (pintype "power_in"))
      (node (ref "U6") (pin "17") (pinfunction "EPAD_17") (pintype "passive"))
      (node (ref "U6") (pin "2") (pinfunction "REFGND_A_2") (pintype "power_in"))
      (node (ref "U6") (pin "3") (pinfunction "REFGND_B_3") (pintype "power_in"))
      (node (ref "U7") (pin "13") (pinfunction "GND_13") (pintype "power_in"))
      (node (ref "U7") (pin "17") (pinfunction "EPAD_17") (pintype "passive"))
      (node (ref "U7") (pin "2") (pinfunction "REFGND_A_2") (pintype "power_in"))
      (node (ref "U7") (pin "3") (pinfunction "REFGND_B_3") (pintype "power_in"))
    )
    (net (code "22") (name "Net-(C2-Pad2)") (class "Default")
      (node (ref "C2") (pin "2") (pinfunction "2_2") (pintype "passive"))
      (node (ref "R30") (pin "2") (pinfunction "2_2") (pintype "passive"))
    )
    (net (code "23") (name "Net-(C4-Pad2)") (class "Default")
      (node (ref "C4") (pin "2") (pinfunction "2_2") (pintype "passive"))
      (node (ref "R3") (pin "2") (pinfunction "2_2") (pintype "passive"))
    )
    (net (code "24") (name "Net-(C21-Pad2)") (class "Default")
      (node (ref "C21") (pin "2") (pinfunction "2_2") (pintype "passive"))
      (node (ref "R55") (pin "2") (pinfunction "2_2") (pintype "passive"))
    )
    (net (code "25") (name "Net-(C22-Pad2)") (class "Default")
      (node (ref "C22") (pin "2") (pinfunction "2_2") (pintype "passive"))
      (node (ref "R56") (pin "2") (pinfunction "2_2") (pintype "passive"))
    )
    (net (code "26") (name "Net-(R31-Pad2)") (class "Default")
      (node (ref "R31") (pin "2") (pinfunction "2_2") (pintype "passive"))
      (node (ref "R52") (pin "1") (pinfunction "1_1") (pintype "passive"))
    )
    (net (code "27") (name "Net-(R34-Pad2)") (class "Default")
      (node (ref "R34") (pin "2") (pinfunction "2_2") (pintype "passive"))
      (node (ref "R54") (pin "1") (pinfunction "1_1") (pintype "passive"))
    )
    (net (code "28") (name "Net-(R35-Pad1)") (class "Default")
      (node (ref "R35") (pin "1") (pinfunction "1_1") (pintype "passive"))
      (node (ref "R51") (pin "1") (pinfunction "1_1") (pintype "passive"))
    )
    (net (code "29") (name "Net-(R36-Pad1)") (class "Default")
      (node (ref "R36") (pin "1") (pinfunction "1_1") (pintype "passive"))
      (node (ref "R53") (pin "1") (pinfunction "1_1") (pintype "passive"))
    )
    (net (code "30") (name "Net-(U1A-IN_A+)") (class "Default")
      (node (ref "C5") (pin "1") (pinfunction "1_1") (pintype "passive"))
      (node (ref "R10") (pin "1") (pinfunction "1_1") (pintype "passive"))
      (node (ref "R4") (pin "2") (pinfunction "2_2") (pintype "passive"))
      (node (ref "U1") (pin "3") (pinfunction "IN_A+_3") (pintype "input"))
    )
    (net (code "31") (name "Net-(U1A-IN_A-)") (class "Default")
      (node (ref "R8") (pin "2") (pinfunction "2_2") (pintype "passive"))
      (node (ref "U1") (pin "1") (pinfunction "OUT_A_1") (pintype "output"))
      (node (ref "U1") (pin "2") (pinfunction "IN_A-_2") (pintype "input"))
    )
    (net (code "32") (name "Net-(U1B-IN_B+)") (class "Default")
      (node (ref "R16") (pin "1") (pinfunction "1_1") (pintype "passive"))
      (node (ref "U1") (pin "5") (pinfunction "IN_B+_5") (pintype "input"))
    )
    (net (code "33") (name "Net-(U1B-IN_B-)") (class "Default")
      (node (ref "R1") (pin "1") (pinfunction "1_1") (pintype "passive"))
      (node (ref "R8") (pin "1") (pinfunction "1_1") (pintype "passive"))
      (node (ref "U1") (pin "6") (pinfunction "IN_B-_6") (pintype "input"))
    )
    (net (code "34") (name "Net-(U1B-OUT_B)") (class "Default")
      (node (ref "C6") (pin "2") (pinfunction "2_2") (pintype "passive"))
      (node (ref "R1") (pin "2") (pinfunction "2_2") (pintype "passive"))
      (node (ref "U1") (pin "7") (pinfunction "OUT_B_7") (pintype "output"))
    )
    (net (code "35") (name "Net-(U2A-IN_A+)") (class "Default")
      (node (ref "C7") (pin "1") (pinfunction "1_1") (pintype "passive"))
      (node (ref "R12") (pin "1") (pinfunction "1_1") (pintype "passive"))
      (node (ref "R6") (pin "2") (pinfunction "2_2") (pintype "passive"))
      (node (ref "U2") (pin "3") (pinfunction "IN_A+_3") (pintype "input"))
    )
    (net (code "36") (name "Net-(U2A-IN_A-)") (class "Default")
      (node (ref "R9") (pin "2") (pinfunction "2_2") (pintype "passive"))
      (node (ref "U2") (pin "1") (pinfunction "OUT_A_1") (pintype "output"))
      (node (ref "U2") (pin "2") (pinfunction "IN_A-_2") (pintype "input"))
    )
    (net (code "37") (name "Net-(U2B-IN_B+)") (class "Default")
      (node (ref "R17") (pin "1") (pinfunction "1_1") (pintype "passive"))
      (node (ref "U2") (pin "5") (pinfunction "IN_B+_5") (pintype "input"))
    )
    (net (code "38") (name "Net-(U2B-IN_B-)") (class "Default")
      (node (ref "R2") (pin "1") (pinfunction "1_1") (pintype "passive"))
      (node (ref "R9") (pin "1") (pinfunction "1_1") (pintype "passive"))
      (node (ref "U2") (pin "6") (pinfunction "IN_B-_6") (pintype "input"))
    )
    (net (code "39") (name "Net-(U2B-OUT_B)") (class "Default")
      (node (ref "C8") (pin "2") (pinfunction "2_2") (pintype "passive"))
      (node (ref "R2") (pin "2") (pinfunction "2_2") (pintype "passive"))
      (node (ref "U2") (pin "7") (pinfunction "OUT_B_7") (pintype "output"))
    )
    (net (code "40") (name "Net-(U3A-IN_A+)") (class "Default")
      (node (ref "C13") (pin "1") (pinfunction "1_1") (pintype "passive"))
      (node (ref "R20") (pin "2") (pinfunction "2_2") (pintype "passive"))
      (node (ref "R28") (pin "1") (pinfunction "1_1") (pintype "passive"))
      (node (ref "U3") (pin "3") (pinfunction "IN_A+_3") (pintype "input"))
    )
    (net (code "41") (name "Net-(U3A-IN_A-)") (class "Default")
      (node (ref "R22") (pin "2") (pinfunction "2_2") (pintype "passive"))
      (node (ref "U3") (pin "1") (pinfunction "OUT_A_1") (pintype "output"))
      (node (ref "U3") (pin "2") (pinfunction "IN_A-_2") (pintype "input"))
    )
    (net (code "42") (name "Net-(U3B-IN_B+)") (class "Default")
      (node (ref "R58") (pin "1") (pinfunction "1_1") (pintype "passive"))
      (node (ref "U3") (pin "5") (pinfunction "IN_B+_5") (pintype "input"))
    )
    (net (code "43") (name "Net-(U3B-IN_B-)") (class "Default")
      (node (ref "R18") (pin "1") (pinfunction "1_1") (pintype "passive"))
      (node (ref "R22") (pin "1") (pinfunction "1_1") (pintype "passive"))
      (node (ref "U3") (pin "6") (pinfunction "IN_B-_6") (pintype "input"))
    )
    (net (code "44") (name "Net-(U3B-OUT_B)") (class "Default")
      (node (ref "C14") (pin "2") (pinfunction "2_2") (pintype "passive"))
      (node (ref "R18") (pin "2") (pinfunction "2_2") (pintype "passive"))
      (node (ref "U3") (pin "7") (pinfunction "OUT_B_7") (pintype "output"))
    )
    (net (code "45") (name "Net-(U4A-IN_A+)") (class "Default")
      (node (ref "C15") (pin "1") (pinfunction "1_1") (pintype "passive"))
      (node (ref "R25") (pin "2") (pinfunction "2_2") (pintype "passive"))
      (node (ref "R59") (pin "1") (pinfunction "1_1") (pintype "passive"))
      (node (ref "U4") (pin "3") (pinfunction "IN_A+_3") (pintype "input"))
    )
    (net (code "46") (name "Net-(U4A-IN_A-)") (class "Default")
      (node (ref "R27") (pin "2") (pinfunction "2_2") (pintype "passive"))
      (node (ref "U4") (pin "1") (pinfunction "OUT_A_1") (pintype "output"))
      (node (ref "U4") (pin "2") (pinfunction "IN_A-_2") (pintype "input"))
    )
    (net (code "47") (name "Net-(U4B-IN_B+)") (class "Default")
      (node (ref "R61") (pin "1") (pinfunction "1_1") (pintype "passive"))
      (node (ref "U4") (pin "5") (pinfunction "IN_B+_5") (pintype "input"))
    )
    (net (code "48") (name "Net-(U4B-IN_B-)") (class "Default")
      (node (ref "R23") (pin "1") (pinfunction "1_1") (pintype "passive"))
      (node (ref "R27") (pin "1") (pinfunction "1_1") (pintype "passive"))
      (node (ref "U4") (pin "6") (pinfunction "IN_B-_6") (pintype "input"))
    )
    (net (code "49") (name "Net-(U4B-OUT_B)") (class "Default")
      (node (ref "C16") (pin "2") (pinfunction "2_2") (pintype "passive"))
      (node (ref "R23") (pin "2") (pinfunction "2_2") (pintype "passive"))
      (node (ref "U4") (pin "7") (pinfunction "OUT_B_7") (pintype "output"))
    )
    (net (code "50") (name "Net-(U6-*CS)") (class "Default")
      (node (ref "R49") (pin "2") (pinfunction "2_2") (pintype "passive"))
      (node (ref "U6") (pin "9") (pinfunction "*CS_9") (pintype "input"))
    )
    (net (code "51") (name "Net-(U6-AINM_A)") (class "Default")
      (node (ref "C23") (pin "1") (pinfunction "1_1") (pintype "passive"))
      (node (ref "R31") (pin "1") (pinfunction "1_1") (pintype "passive"))
      (node (ref "U6") (pin "16") (pinfunction "AINM_A_16") (pintype "input"))
    )
    (net (code "52") (name "Net-(U6-AINM_B)") (class "Default")
      (node (ref "C25") (pin "1") (pinfunction "1_1") (pintype "passive"))
      (node (ref "R35") (pin "2") (pinfunction "2_2") (pintype "passive"))
      (node (ref "U6") (pin "5") (pinfunction "AINM_B_5") (pintype "input"))
    )
    (net (code "53") (name "Net-(U6-AINP_A)") (class "Default")
      (node (ref "C23") (pin "2") (pinfunction "2_2") (pintype "passive"))
      (node (ref "R37") (pin "1") (pinfunction "1_1") (pintype "passive"))
      (node (ref "U6") (pin "15") (pinfunction "AINP_A_15") (pintype "input"))
    )
    (net (code "54") (name "Net-(U6-AINP_B)") (class "Default")
      (node (ref "C25") (pin "2") (pinfunction "2_2") (pintype "passive"))
      (node (ref "R41") (pin "2") (pinfunction "2_2") (pintype "passive"))
      (node (ref "U6") (pin "6") (pinfunction "AINP_B_6") (pintype "input"))
    )
    (net (code "55") (name "Net-(U6-REFIO_A)") (class "Default")
      (node (ref "R3") (pin "1") (pinfunction "1_1") (pintype "passive"))
      (node (ref "R30") (pin "1") (pinfunction "1_1") (pintype "passive"))
      (node (ref "R32") (pin "2") (pinfunction "2_2") (pintype "passive"))
      (node (ref "U6") (pin "1") (pinfunction "REFIO_A_1") (pintype "bidirectional"))
      (node (ref "U6") (pin "4") (pinfunction "REFIO_B_4") (pintype "bidirectional"))
    )
    (net (code "56") (name "Net-(U6-SCLK)") (class "Default")
      (node (ref "R47") (pin "2") (pinfunction "2_2") (pintype "passive"))
      (node (ref "U6") (pin "10") (pinfunction "SCLK_10") (pintype "input"))
    )
    (net (code "57") (name "Net-(U6-SDI)") (class "Default")
      (node (ref "R45") (pin "1") (pinfunction "1_1") (pintype "passive"))
      (node (ref "U6") (pin "8") (pinfunction "SDI_8") (pintype "input"))
    )
    (net (code "58") (name "Net-(U6-SDO_A)") (class "Default")
      (node (ref "R43") (pin "2") (pinfunction "2_2") (pintype "passive"))
      (node (ref "U6") (pin "11") (pinfunction "SDO_A_11") (pintype "output"))
    )
    (net (code "59") (name "Net-(U6-SDO_B)") (class "Default")
      (node (ref "R39") (pin "2") (pinfunction "2_2") (pintype "passive"))
      (node (ref "U6") (pin "12") (pinfunction "SDO_B_12") (pintype "output"))
    )
    (net (code "60") (name "Net-(U7-*CS)") (class "Default")
      (node (ref "R50") (pin "2") (pinfunction "2_2") (pintype "passive"))
      (node (ref "U7") (pin "9") (pinfunction "*CS_9") (pintype "input"))
    )
    (net (code "61") (name "Net-(U7-AINM_A)") (class "Default")
      (node (ref "C24") (pin "1") (pinfunction "1_1") (pintype "passive"))
      (node (ref "R34") (pin "1") (pinfunction "1_1") (pintype "passive"))
      (node (ref "U7") (pin "16") (pinfunction "AINM_A_16") (pintype "input"))
    )
    (net (code "62") (name "Net-(U7-AINM_B)") (class "Default")
      (node (ref "C26") (pin "1") (pinfunction "1_1") (pintype "passive"))
      (node (ref "R36") (pin "2") (pinfunction "2_2") (pintype "passive"))
      (node (ref "U7") (pin "5") (pinfunction "AINM_B_5") (pintype "input"))
    )
    (net (code "63") (name "Net-(U7-AINP_A)") (class "Default")
      (node (ref "C24") (pin "2") (pinfunction "2_2") (pintype "passive"))
      (node (ref "R38") (pin "1") (pinfunction "1_1") (pintype "passive"))
      (node (ref "U7") (pin "15") (pinfunction "AINP_A_15") (pintype "input"))
    )
    (net (code "64") (name "Net-(U7-AINP_B)") (class "Default")
      (node (ref "C26") (pin "2") (pinfunction "2_2") (pintype "passive"))
      (node (ref "R42") (pin "2") (pinfunction "2_2") (pintype "passive"))
      (node (ref "U7") (pin "6") (pinfunction "AINP_B_6") (pintype "input"))
    )
    (net (code "65") (name "Net-(U7-REFIO_A)") (class "Default")
      (node (ref "R33") (pin "2") (pinfunction "2_2") (pintype "passive"))
      (node (ref "R55") (pin "1") (pinfunction "1_1") (pintype "passive"))
      (node (ref "R56") (pin "1") (pinfunction "1_1") (pintype "passive"))
      (node (ref "U7") (pin "1") (pinfunction "REFIO_A_1") (pintype "bidirectional"))
      (node (ref "U7") (pin "4") (pinfunction "REFIO_B_4") (pintype "bidirectional"))
    )
    (net (code "66") (name "Net-(U7-SCLK)") (class "Default")
      (node (ref "R48") (pin "2") (pinfunction "2_2") (pintype "passive"))
      (node (ref "U7") (pin "10") (pinfunction "SCLK_10") (pintype "input"))
    )
    (net (code "67") (name "Net-(U7-SDI)") (class "Default")
      (node (ref "R46") (pin "1") (pinfunction "1_1") (pintype "passive"))
      (node (ref "U7") (pin "8") (pinfunction "SDI_8") (pintype "input"))
    )
    (net (code "68") (name "Net-(U7-SDO_A)") (class "Default")
      (node (ref "R44") (pin "2") (pinfunction "2_2") (pintype "passive"))
      (node (ref "U7") (pin "11") (pinfunction "SDO_A_11") (pintype "output"))
    )
    (net (code "69") (name "Net-(U7-SDO_B)") (class "Default")
      (node (ref "R40") (pin "2") (pinfunction "2_2") (pintype "passive"))
      (node (ref "U7") (pin "12") (pinfunction "SDO_B_12") (pintype "output"))
    )
  )
)
